# sensor_TEMT6000.net
KiCad netlist of a schematic drawn in EAGLE
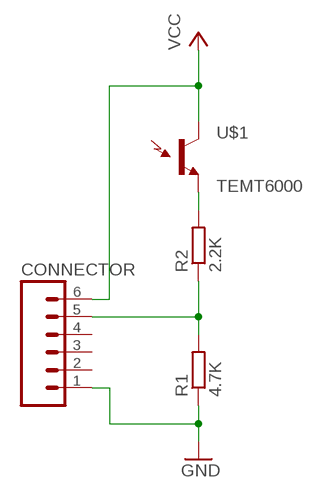
[diagram p0: schematic, sheet 1]

(export (version "E")
  (design (tool "Eeschema 10.0.6"))
  (components
    (comp (ref "CONNECTOR")
      (value "M06_90SIP")
      (footprint "eagle-import:1X06_90")
      (libsource (lib "eagle-import") (part "M06_90SIP"))
    )
    (comp (ref "R1")
      (value "4.7K")
      (footprint "eagle-import:0204_7")
      (libsource (lib "eagle-import") (part "R-EU_0204/7"))
    )
    (comp (ref "R2")
      (value "2.2K")
      (footprint "eagle-import:0204_7")
      (libsource (lib "eagle-import") (part "R-EU_0204/7"))
    )
    (comp (ref "U$1")
      (value "TEMT6000")
      (footprint "eagle-import:TEMT6000-SEN")
      (libsource (lib "eagle-import") (part "TEMT6000"))
    )
  )
  (nets
    (net (code "1") (name "GND") (class "Default")
      (node (ref "CONNECTOR") (pin "1") (pinfunction "1_1") (pintype "passive"))
      (node (ref "R1") (pin "1") (pinfunction "1_1") (pintype "passive"))
    )
    (net (code "2") (name "Net-(CONNECTOR-Pad5)") (class "Default")
      (node (ref "CONNECTOR") (pin "5") (pinfunction "5_5") (pintype "passive"))
      (node (ref "R1") (pin "2") (pinfunction "2_2") (pintype "passive"))
      (node (ref "R2") (pin "1") (pinfunction "1_1") (pintype "passive"))
    )
    (net (code "3") (name "Net-(U$1-E1)") (class "Default")
      (node (ref "R2") (pin "2") (pinfunction "2_2") (pintype "passive"))
      (node (ref "U$1") (pin "EMITTER") (pinfunction "E1_EMITTER") (pintype "passive"))
    )
    (net (code "4") (name "VCC") (class "Default")
      (node (ref "CONNECTOR") (pin "6") (pinfunction "6_6") (pintype "passive"))
      (node (ref "U$1") (pin "COLLECTOR") (pinfunction "C1_COLLECTOR") (pintype "passive"))
    )
    (net (code "5") (name "unconnected-(CONNECTOR-Pad2)") (class "Default")
      (node (ref "CONNECTOR") (pin "2") (pinfunction "2_2") (pintype "passive"))
    )
    (net (code "6") (name "unconnected-(CONNECTOR-Pad3)") (class "Default")
      (node (ref "CONNECTOR") (pin "3") (pinfunction "3_3") (pintype "passive"))
    )
    (net (code "7") (name "unconnected-(CONNECTOR-Pad4)") (class "Default")
      (node (ref "CONNECTOR") (pin "4") (pinfunction "4_4") (pintype "passive"))
    )
  )
)
